# MCU.net
KiCad netlist of a schematic drawn in Altium Designer
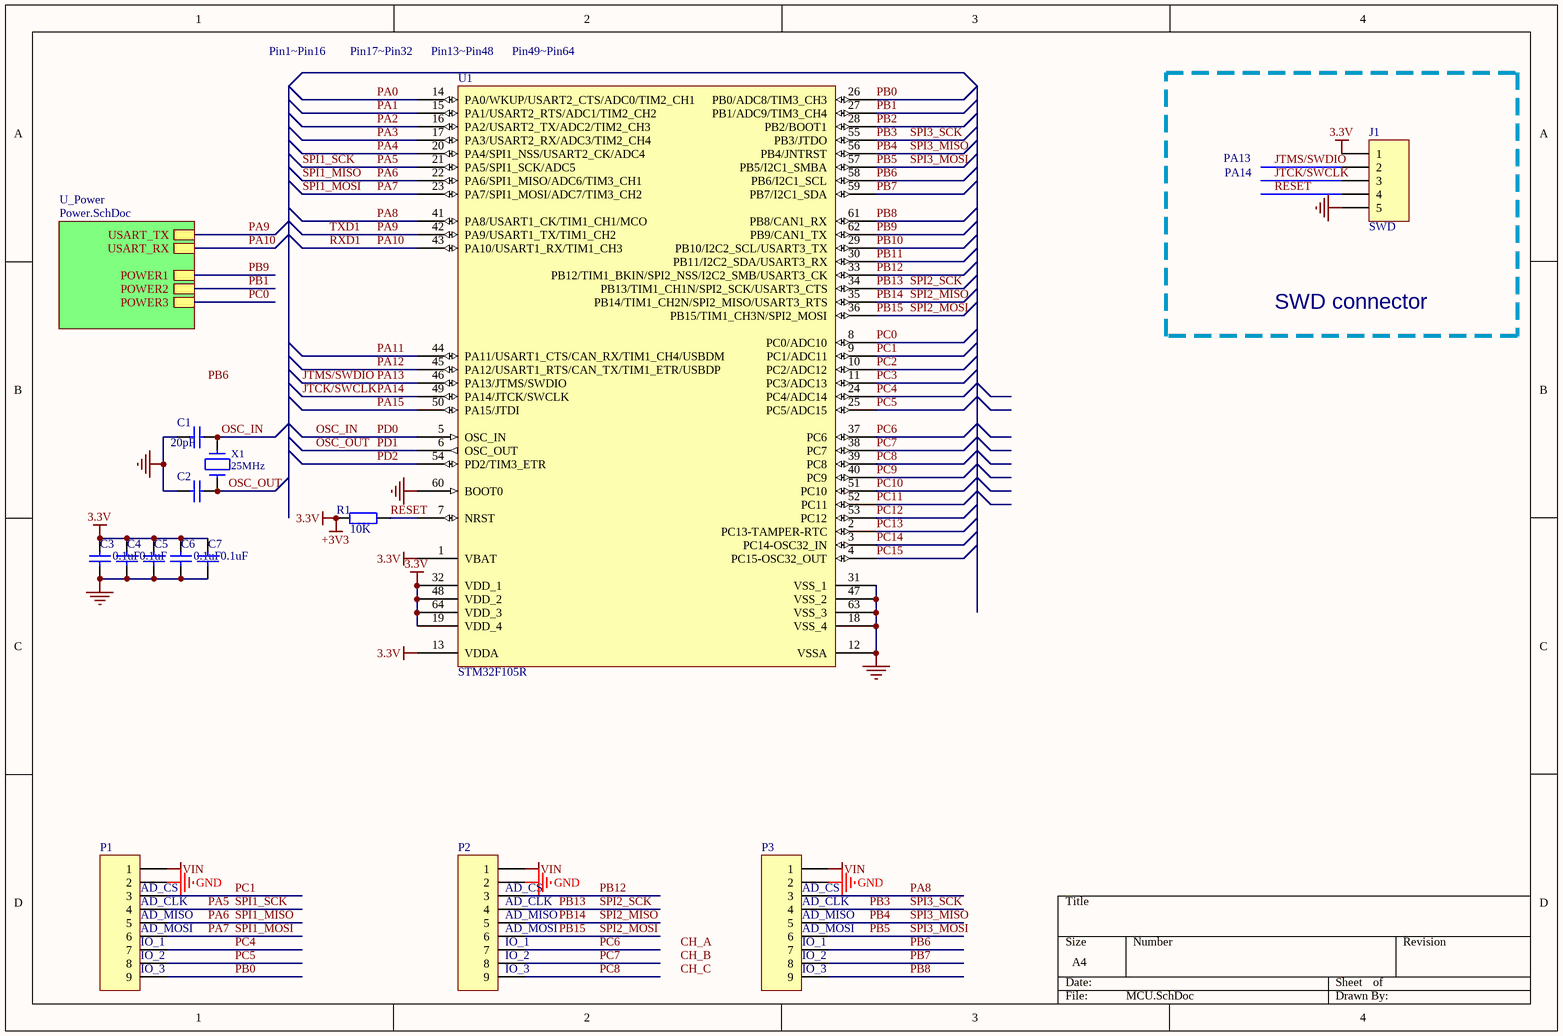
[diagram p0: MCU.SchDoc]

(export (version "E")
  (design (tool "Eeschema 10.0.6"))
  (components
    (comp (ref "C1")
      (value "20pF")
      (footprint "C2012")
      (description "Capacitor")
      (fields (field (name "PUBLISHER") "Altium Limited"))
      (libsource (lib "*") (part "Cap"))
    )
    (comp (ref "C2")
      (value "20pF")
      (footprint "C2012")
      (description "Capacitor")
      (fields (field (name "PUBLISHER") "Altium Limited"))
      (libsource (lib "*") (part "Cap"))
    )
    (comp (ref "C3")
      (value "0.1uF")
      (footprint "C2012")
      (description "Capacitor")
      (fields (field (name "PUBLISHER") "Altium Limited"))
      (libsource (lib "*") (part "Cap"))
    )
    (comp (ref "C4")
      (value "0.1uF")
      (footprint "C2012")
      (description "Capacitor")
      (fields (field (name "PUBLISHER") "Altium Limited"))
      (libsource (lib "*") (part "Cap"))
    )
    (comp (ref "C5")
      (value "0.1uF")
      (footprint "C2012")
      (description "Capacitor")
      (fields (field (name "PUBLISHER") "Altium Limited"))
      (libsource (lib "*") (part "Cap"))
    )
    (comp (ref "C6")
      (value "0.1uF")
      (footprint "C2012")
      (description "Capacitor")
      (fields (field (name "PUBLISHER") "Altium Limited"))
      (libsource (lib "*") (part "Cap"))
    )
    (comp (ref "C7")
      (value "0.1uF")
      (footprint "C2012")
      (description "Capacitor")
      (fields (field (name "PUBLISHER") "Altium Limited"))
      (libsource (lib "*") (part "Cap"))
    )
    (comp (ref "J1")
      (value "SWD")
      (footprint "ch2.5/5")
      (description "Header, 5-Pin")
      (fields (field (name "PUBLISHER") "Altium Limited"))
      (libsource (lib "Miscellaneous Connectors") (part "Header 5"))
    )
    (comp (ref "P1")
      (value "Header 9")
      (footprint "FPC-9B")
      (description "Header, 9-Pin")
      (fields (field (name "PUBLISHER") "Altium Limited"))
      (libsource (lib "Miscellaneous Connectors") (part "Header 9"))
    )
    (comp (ref "P2")
      (value "Header 9")
      (footprint "FPC-9B")
      (description "Header, 9-Pin")
      (fields (field (name "PUBLISHER") "Altium Limited"))
      (libsource (lib "Miscellaneous Connectors") (part "Header 9"))
    )
    (comp (ref "P3")
      (value "Header 9")
      (footprint "FPC-9B")
      (description "Header, 9-Pin")
      (fields (field (name "PUBLISHER") "Altium Limited"))
      (libsource (lib "Miscellaneous Connectors") (part "Header 9"))
    )
    (comp (ref "R1")
      (value "10K")
      (footprint "2012")
      (description "Resistor")
      (fields (field (name "PUBLISHER") "Altium Limited"))
      (libsource (lib "*") (part "Res2"))
    )
    (comp (ref "U1")
      (value "STM32F105R")
      (footprint "LQFP64_M")
      (libsource (lib "Schlib1") (part "STM32F105R"))
    )
    (comp (ref "X1") (value "25MHz") (footprint "SMD2_50X32") (libsource (lib "*") (part "CRYSTAL")))
  )
  (nets
    (net (code "1") (name "+3V3") (class "Default")
      (node (ref "C3") (pin "2") (pinfunction "2_2") (pintype "passive"))
      (node (ref "C4") (pin "2") (pinfunction "2_2") (pintype "passive"))
      (node (ref "C5") (pin "2") (pinfunction "2_2") (pintype "passive"))
      (node (ref "C6") (pin "2") (pinfunction "2_2") (pintype "passive"))
      (node (ref "C7") (pin "2") (pinfunction "2_2") (pintype "passive"))
      (node (ref "J1") (pin "1") (pinfunction "1_1") (pintype "passive"))
      (node (ref "R1") (pin "1") (pinfunction "1_1") (pintype "passive"))
      (node (ref "U1") (pin "1") (pinfunction "VBAT_1") (pintype "power_in"))
      (node (ref "U1") (pin "13") (pinfunction "VDDA_13") (pintype "power_in"))
      (node (ref "U1") (pin "19") (pinfunction "VDD_4_19") (pintype "power_in"))
      (node (ref "U1") (pin "32") (pinfunction "VDD_1_32") (pintype "power_in"))
      (node (ref "U1") (pin "48") (pinfunction "VDD_2_48") (pintype "power_in"))
      (node (ref "U1") (pin "64") (pinfunction "VDD_3_64") (pintype "power_in"))
    )
    (net (code "5") (name "/JTCK{slash}SWCLK") (class "Default")
      (node (ref "J1") (pin "3") (pinfunction "3_3") (pintype "passive"))
      (node (ref "U1") (pin "49") (pinfunction "PA14/JTCK/SWCLK_49") (pintype "bidirectional"))
    )
    (net (code "6") (name "/JTMS{slash}SWDIO") (class "Default")
      (node (ref "J1") (pin "2") (pinfunction "2_2") (pintype "passive"))
      (node (ref "U1") (pin "46") (pinfunction "PA13/JTMS/SWDIO_46") (pintype "bidirectional"))
    )
    (net (code "7") (name "/OSC_IN") (class "Default")
      (node (ref "C1") (pin "1") (pinfunction "1_1") (pintype "passive"))
      (node (ref "U1") (pin "5") (pinfunction "OSC_IN_5") (pintype "input"))
      (node (ref "X1") (pin "2") (pintype "passive"))
    )
    (net (code "8") (name "/OSC_OUT") (class "Default")
      (node (ref "C2") (pin "1") (pinfunction "1_1") (pintype "passive"))
      (node (ref "U1") (pin "6") (pinfunction "OSC_OUT_6") (pintype "output"))
      (node (ref "X1") (pin "1") (pintype "passive"))
    )
    (net (code "9") (name "/PA0") (class "Default")
      (node (ref "U1") (pin "14") (pinfunction "PA0/WKUP/USART2_CTS/ADC0/TIM2_CH1_14") (pintype "bidirectional"))
    )
    (net (code "10") (name "/PA1") (class "Default")
      (node (ref "U1") (pin "15") (pinfunction "PA1/USART2_RTS/ADC1/TIM2_CH2_15") (pintype "bidirectional"))
    )
    (net (code "11") (name "/PA2") (class "Default")
      (node (ref "U1") (pin "16") (pinfunction "PA2/USART2_TX/ADC2/TIM2_CH3_16") (pintype "bidirectional"))
    )
    (net (code "12") (name "/PA3") (class "Default")
      (node (ref "U1") (pin "17") (pinfunction "PA3/USART2_RX/ADC3/TIM2_CH4_17") (pintype "bidirectional"))
    )
    (net (code "13") (name "/PA4") (class "Default")
      (node (ref "U1") (pin "20") (pinfunction "PA4/SPI1_NSS/USART2_CK/ADC4_20") (pintype "bidirectional"))
    )
    (net (code "14") (name "/PA5") (class "Default")
      (node (ref "P1") (pin "4") (pinfunction "4_4") (pintype "passive"))
      (node (ref "U1") (pin "21") (pinfunction "PA5/SPI1_SCK/ADC5_21") (pintype "bidirectional"))
    )
    (net (code "15") (name "/PA6") (class "Default")
      (node (ref "P1") (pin "5") (pinfunction "5_5") (pintype "passive"))
      (node (ref "U1") (pin "22") (pinfunction "PA6/SPI1_MISO/ADC6/TIM3_CH1_22") (pintype "bidirectional"))
    )
    (net (code "16") (name "/PA7") (class "Default")
      (node (ref "P1") (pin "6") (pinfunction "6_6") (pintype "passive"))
      (node (ref "U1") (pin "23") (pinfunction "PA7/SPI1_MOSI/ADC7/TIM3_CH2_23") (pintype "bidirectional"))
    )
    (net (code "17") (name "/PA8") (class "Default")
      (node (ref "P3") (pin "3") (pinfunction "3_3") (pintype "passive"))
      (node (ref "U1") (pin "41") (pinfunction "PA8/USART1_CK/TIM1_CH1/MCO_41") (pintype "bidirectional"))
    )
    (net (code "18") (name "/PA9") (class "Default")
      (node (ref "U1") (pin "42") (pinfunction "PA9/USART1_TX/TIM1_CH2_42") (pintype "bidirectional"))
    )
    (net (code "19") (name "/PA10") (class "Default")
      (node (ref "U1") (pin "43") (pinfunction "PA10/USART1_RX/TIM1_CH3_43") (pintype "bidirectional"))
    )
    (net (code "20") (name "/PA11") (class "Default")
      (node (ref "U1") (pin "44") (pinfunction "PA11/USART1_CTS/CAN_RX/TIM1_CH4/USBDM_44") (pintype "bidirectional"))
    )
    (net (code "21") (name "/PA12") (class "Default")
      (node (ref "U1") (pin "45") (pinfunction "PA12/USART1_RTS/CAN_TX/TIM1_ETR/USBDP_45") (pintype "bidirectional"))
    )
    (net (code "22") (name "/PA15") (class "Default")
      (node (ref "U1") (pin "50") (pinfunction "PA15/JTDI_50") (pintype "bidirectional"))
    )
    (net (code "23") (name "/PB0") (class "Default")
      (node (ref "P1") (pin "9") (pinfunction "9_9") (pintype "passive"))
      (node (ref "U1") (pin "26") (pinfunction "PB0/ADC8/TIM3_CH3_26") (pintype "bidirectional"))
    )
    (net (code "24") (name "/PB1") (class "Default")
      (node (ref "U1") (pin "27") (pinfunction "PB1/ADC9/TIM3_CH4_27") (pintype "bidirectional"))
    )
    (net (code "25") (name "/PB2") (class "Default")
      (node (ref "U1") (pin "28") (pinfunction "PB2/BOOT1_28") (pintype "bidirectional"))
    )
    (net (code "26") (name "/PB3") (class "Default")
      (node (ref "P3") (pin "4") (pinfunction "4_4") (pintype "passive"))
      (node (ref "U1") (pin "55") (pinfunction "PB3/JTDO_55") (pintype "bidirectional"))
    )
    (net (code "27") (name "/PB4") (class "Default")
      (node (ref "P3") (pin "5") (pinfunction "5_5") (pintype "passive"))
      (node (ref "U1") (pin "56") (pinfunction "PB4/JNTRST_56") (pintype "bidirectional"))
    )
    (net (code "28") (name "/PB5") (class "Default")
      (node (ref "P3") (pin "6") (pinfunction "6_6") (pintype "passive"))
      (node (ref "U1") (pin "57") (pinfunction "PB5/I2C1_SMBA_57") (pintype "bidirectional"))
    )
    (net (code "29") (name "/PB6") (class "Default")
      (node (ref "P3") (pin "7") (pinfunction "7_7") (pintype "passive"))
      (node (ref "U1") (pin "58") (pinfunction "PB6/I2C1_SCL_58") (pintype "bidirectional"))
    )
    (net (code "30") (name "/PB7") (class "Default")
      (node (ref "P3") (pin "8") (pinfunction "8_8") (pintype "passive"))
      (node (ref "U1") (pin "59") (pinfunction "PB7/I2C1_SDA_59") (pintype "bidirectional"))
    )
    (net (code "31") (name "/PB8") (class "Default")
      (node (ref "P3") (pin "9") (pinfunction "9_9") (pintype "passive"))
      (node (ref "U1") (pin "61") (pinfunction "PB8/CAN1_RX_61") (pintype "bidirectional"))
    )
    (net (code "32") (name "/PB9") (class "Default")
      (node (ref "U1") (pin "62") (pinfunction "PB9/CAN1_TX_62") (pintype "bidirectional"))
    )
    (net (code "33") (name "/PB10") (class "Default")
      (node (ref "U1") (pin "29") (pinfunction "PB10/I2C2_SCL/USART3_TX_29") (pintype "bidirectional"))
    )
    (net (code "34") (name "/PB11") (class "Default")
      (node (ref "U1") (pin "30") (pinfunction "PB11/I2C2_SDA/USART3_RX_30") (pintype "bidirectional"))
    )
    (net (code "35") (name "/PB12") (class "Default")
      (node (ref "P2") (pin "3") (pinfunction "3_3") (pintype "passive"))
      (node (ref "U1") (pin "33") (pinfunction "PB12/TIM1_BKIN/SPI2_NSS/I2C2_SMB/USART3_CK_33") (pintype "bidirectional"))
    )
    (net (code "36") (name "/PB13") (class "Default")
      (node (ref "P2") (pin "4") (pinfunction "4_4") (pintype "passive"))
      (node (ref "U1") (pin "34") (pinfunction "PB13/TIM1_CH1N/SPI2_SCK/USART3_CTS_34") (pintype "bidirectional"))
    )
    (net (code "37") (name "/PB14") (class "Default")
      (node (ref "P2") (pin "5") (pinfunction "5_5") (pintype "passive"))
      (node (ref "U1") (pin "35") (pinfunction "PB14/TIM1_CH2N/SPI2_MISO/USART3_RTS_35") (pintype "bidirectional"))
    )
    (net (code "38") (name "/PB15") (class "Default")
      (node (ref "P2") (pin "6") (pinfunction "6_6") (pintype "passive"))
      (node (ref "U1") (pin "36") (pinfunction "PB15/TIM1_CH3N/SPI2_MOSI_36") (pintype "bidirectional"))
    )
    (net (code "39") (name "/PC0") (class "Default")
      (node (ref "U1") (pin "8") (pinfunction "PC0/ADC10_8") (pintype "bidirectional"))
    )
    (net (code "40") (name "/PC1") (class "Default")
      (node (ref "P1") (pin "3") (pinfunction "3_3") (pintype "passive"))
      (node (ref "U1") (pin "9") (pinfunction "PC1/ADC11_9") (pintype "bidirectional"))
    )
    (net (code "41") (name "/PC2") (class "Default")
      (node (ref "U1") (pin "10") (pinfunction "PC2/ADC12_10") (pintype "bidirectional"))
    )
    (net (code "42") (name "/PC3") (class "Default")
      (node (ref "U1") (pin "11") (pinfunction "PC3/ADC13_11") (pintype "bidirectional"))
    )
    (net (code "43") (name "/PC4") (class "Default")
      (node (ref "P1") (pin "7") (pinfunction "7_7") (pintype "passive"))
      (node (ref "U1") (pin "24") (pinfunction "PC4/ADC14_24") (pintype "bidirectional"))
    )
    (net (code "44") (name "/PC5") (class "Default")
      (node (ref "P1") (pin "8") (pinfunction "8_8") (pintype "passive"))
      (node (ref "U1") (pin "25") (pinfunction "PC5/ADC15_25") (pintype "bidirectional"))
    )
    (net (code "45") (name "/PC6") (class "Default")
      (node (ref "P2") (pin "7") (pinfunction "7_7") (pintype "passive"))
      (node (ref "U1") (pin "37") (pinfunction "PC6_37") (pintype "bidirectional"))
    )
    (net (code "46") (name "/PC7") (class "Default")
      (node (ref "P2") (pin "8") (pinfunction "8_8") (pintype "passive"))
      (node (ref "U1") (pin "38") (pinfunction "PC7_38") (pintype "bidirectional"))
    )
    (net (code "47") (name "/PC8") (class "Default")
      (node (ref "P2") (pin "9") (pinfunction "9_9") (pintype "passive"))
      (node (ref "U1") (pin "39") (pinfunction "PC8_39") (pintype "bidirectional"))
    )
    (net (code "48") (name "/PC9") (class "Default")
      (node (ref "U1") (pin "40") (pinfunction "PC9_40") (pintype "bidirectional"))
    )
    (net (code "49") (name "/PC10") (class "Default")
      (node (ref "U1") (pin "51") (pinfunction "PC10_51") (pintype "bidirectional"))
    )
    (net (code "50") (name "/PC11") (class "Default")
      (node (ref "U1") (pin "52") (pinfunction "PC11_52") (pintype "bidirectional"))
    )
    (net (code "51") (name "/PC12") (class "Default")
      (node (ref "U1") (pin "53") (pinfunction "PC12_53") (pintype "bidirectional"))
    )
    (net (code "52") (name "/PC13") (class "Default")
      (node (ref "U1") (pin "2") (pinfunction "PC13-TAMPER-RTC_2") (pintype "bidirectional"))
    )
    (net (code "53") (name "/PC14") (class "Default")
      (node (ref "U1") (pin "3") (pinfunction "PC14-OSC32_IN_3") (pintype "bidirectional"))
    )
    (net (code "54") (name "/PC15") (class "Default")
      (node (ref "U1") (pin "4") (pinfunction "PC15-OSC32_OUT_4") (pintype "bidirectional"))
    )
    (net (code "55") (name "/PD2") (class "Default")
      (node (ref "U1") (pin "54") (pinfunction "PD2/TIM3_ETR_54") (pintype "bidirectional"))
    )
    (net (code "56") (name "/RESET") (class "Default")
      (node (ref "J1") (pin "4") (pinfunction "4_4") (pintype "passive"))
      (node (ref "R1") (pin "2") (pinfunction "2_2") (pintype "passive"))
      (node (ref "U1") (pin "7") (pinfunction "NRST_7") (pintype "bidirectional"))
    )
    (net (code "57") (name "GND") (class "Default")
      (node (ref "C1") (pin "2") (pinfunction "2_2") (pintype "passive"))
      (node (ref "C2") (pin "2") (pinfunction "2_2") (pintype "passive"))
      (node (ref "C3") (pin "1") (pinfunction "1_1") (pintype "passive"))
      (node (ref "C4") (pin "1") (pinfunction "1_1") (pintype "passive"))
      (node (ref "C5") (pin "1") (pinfunction "1_1") (pintype "passive"))
      (node (ref "C6") (pin "1") (pinfunction "1_1") (pintype "passive"))
      (node (ref "C7") (pin "1") (pinfunction "1_1") (pintype "passive"))
      (node (ref "J1") (pin "5") (pinfunction "5_5") (pintype "passive"))
      (node (ref "P1") (pin "2") (pinfunction "2_2") (pintype "passive"))
      (node (ref "P2") (pin "2") (pinfunction "2_2") (pintype "passive"))
      (node (ref "P3") (pin "2") (pinfunction "2_2") (pintype "passive"))
      (node (ref "U1") (pin "12") (pinfunction "VSSA_12") (pintype "power_in"))
      (node (ref "U1") (pin "18") (pinfunction "VSS_4_18") (pintype "power_in"))
      (node (ref "U1") (pin "31") (pinfunction "VSS_1_31") (pintype "power_in"))
      (node (ref "U1") (pin "47") (pinfunction "VSS_2_47") (pintype "power_in"))
      (node (ref "U1") (pin "60") (pinfunction "BOOT0_60") (pintype "input"))
      (node (ref "U1") (pin "63") (pinfunction "VSS_3_63") (pintype "power_in"))
    )
    (net (code "58") (name "VIN") (class "Default")
      (node (ref "P1") (pin "1") (pinfunction "1_1") (pintype "passive"))
      (node (ref "P2") (pin "1") (pinfunction "1_1") (pintype "passive"))
      (node (ref "P3") (pin "1") (pinfunction "1_1") (pintype "passive"))
    )
  )
)
